# Sheet2_Power_Supply.net
KiCad netlist of a schematic drawn in Altium Designer
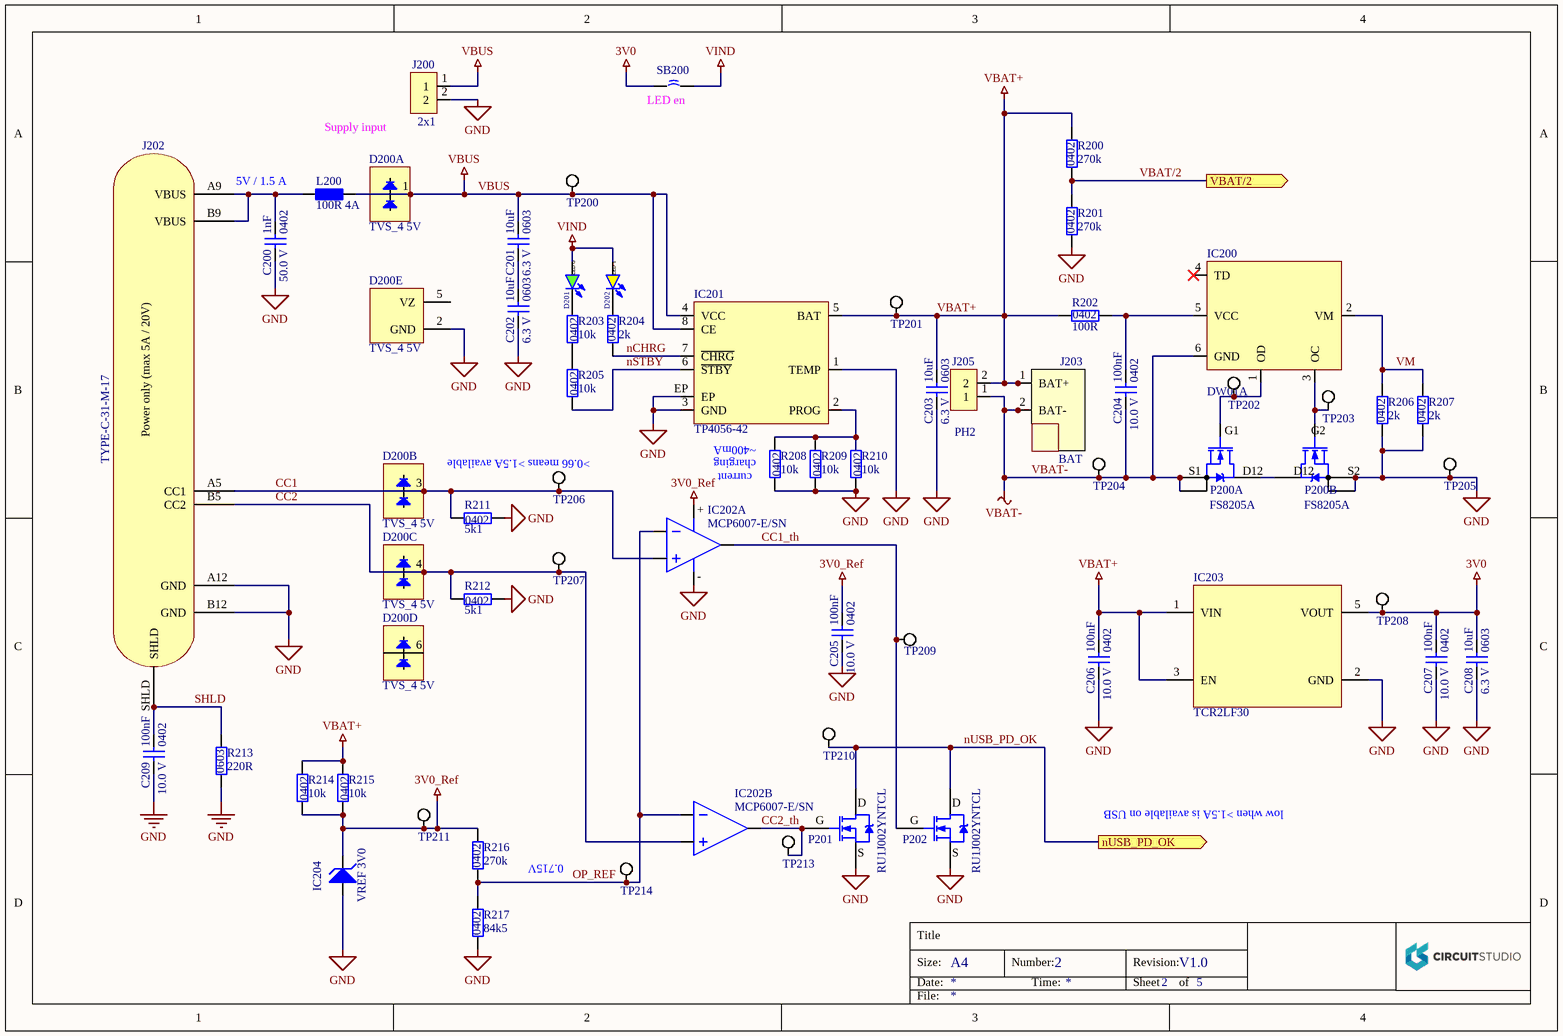
[diagram p0: Sheet2_Power_Supply.SchDoc]

(export (version "E")
  (design (tool "Eeschema 10.0.6"))
  (components
    (comp (ref "C200")
      (value "C 1nF 0402 50V")
      (footprint "0402")
      (description "CAP CER 1000PF 50V C0G/NP0 0402")
      (fields
        (field (name "MANUFACTURER") "Murata Electronics")
        (field (name "MANUFACTURER PART NUMBER") "GRM1555C1H102JA01J")
        (field (name "CAPACITANCE") "1nF")
        (field (name "VOLTAGE") "50.0 V")
      )
      (libsource (lib "CS_Part_Library") (part "CAP_1nF_50V_0402"))
    )
    (comp (ref "C201")
      (value "C 10uF 0603 6.3V")
      (footprint "0603")
      (description "CAP CER 10UF 6.3V X5R 0603")
      (fields
        (field (name "MANUFACTURER") "Taiyo Yuden")
        (field (name "MANUFACTURER PART NUMBER") "JMK107ABJ106MA-T")
        (field (name "CAPACITANCE") "10uF")
        (field (name "VOLTAGE") "6.3 V")
      )
      (libsource (lib "CS_Part_Library") (part "CAP_10uF_6V3_0603"))
    )
    (comp (ref "C202")
      (value "C 10uF 0603 6.3V")
      (footprint "0603")
      (description "CAP CER 10UF 6.3V X5R 0603")
      (fields
        (field (name "MANUFACTURER") "Taiyo Yuden")
        (field (name "MANUFACTURER PART NUMBER") "JMK107ABJ106MA-T")
        (field (name "CAPACITANCE") "10uF")
        (field (name "VOLTAGE") "6.3 V")
      )
      (libsource (lib "CS_Part_Library") (part "CAP_10uF_6V3_0603"))
    )
    (comp (ref "C203")
      (value "C 10uF 0603 6.3V")
      (footprint "0603")
      (description "CAP CER 10UF 6.3V X5R 0603")
      (fields
        (field (name "MANUFACTURER") "Taiyo Yuden")
        (field (name "MANUFACTURER PART NUMBER") "JMK107ABJ106MA-T")
        (field (name "CAPACITANCE") "10uF")
        (field (name "VOLTAGE") "6.3 V")
      )
      (libsource (lib "CS_Part_Library") (part "CAP_10uF_6V3_0603"))
    )
    (comp (ref "C204")
      (value "C 100nF 0402 10V")
      (footprint "0402")
      (description "CAP CER 0.1UF 10V X5R 0402")
      (fields
        (field (name "MANUFACTURER") "Samsung Electro-Mechanics")
        (field (name "MANUFACTURER PART NUMBER") "CL05A104MP5NNNC")
        (field (name "CAPACITANCE") "100nF")
        (field (name "VOLTAGE") "10.0 V")
      )
      (libsource (lib "CS_Part_Library") (part "CAP_100nF_10V_0402"))
    )
    (comp (ref "C205")
      (value "C 100nF 0402 10V")
      (footprint "0402")
      (description "CAP CER 0.1UF 10V X5R 0402")
      (fields
        (field (name "MANUFACTURER") "Samsung Electro-Mechanics")
        (field (name "MANUFACTURER PART NUMBER") "CL05A104MP5NNNC")
        (field (name "CAPACITANCE") "100nF")
        (field (name "VOLTAGE") "10.0 V")
      )
      (libsource (lib "CS_Part_Library") (part "CAP_100nF_10V_0402"))
    )
    (comp (ref "C206")
      (value "C 100nF 0402 10V")
      (footprint "0402")
      (description "CAP CER 0.1UF 10V X5R 0402")
      (fields
        (field (name "MANUFACTURER") "Samsung Electro-Mechanics")
        (field (name "MANUFACTURER PART NUMBER") "CL05A104MP5NNNC")
        (field (name "CAPACITANCE") "100nF")
        (field (name "VOLTAGE") "10.0 V")
      )
      (libsource (lib "CS_Part_Library") (part "CAP_100nF_10V_0402"))
    )
    (comp (ref "C207")
      (value "C 100nF 0402 10V")
      (footprint "0402")
      (description "CAP CER 0.1UF 10V X5R 0402")
      (fields
        (field (name "MANUFACTURER") "Samsung Electro-Mechanics")
        (field (name "MANUFACTURER PART NUMBER") "CL05A104MP5NNNC")
        (field (name "CAPACITANCE") "100nF")
        (field (name "VOLTAGE") "10.0 V")
      )
      (libsource (lib "CS_Part_Library") (part "CAP_100nF_10V_0402"))
    )
    (comp (ref "C208")
      (value "C 10uF 0603 6.3V")
      (footprint "0603")
      (description "CAP CER 10UF 6.3V X5R 0603")
      (fields
        (field (name "MANUFACTURER") "Taiyo Yuden")
        (field (name "MANUFACTURER PART NUMBER") "JMK107ABJ106MA-T")
        (field (name "CAPACITANCE") "10uF")
        (field (name "VOLTAGE") "6.3 V")
      )
      (libsource (lib "CS_Part_Library") (part "CAP_10uF_6V3_0603"))
    )
    (comp (ref "C209")
      (value "C 100nF 0402 10V")
      (footprint "0402")
      (description "CAP CER 0.1UF 10V X5R 0402")
      (fields
        (field (name "MANUFACTURER") "Samsung Electro-Mechanics")
        (field (name "MANUFACTURER PART NUMBER") "CL05A104MP5NNNC")
        (field (name "CAPACITANCE") "100nF")
        (field (name "VOLTAGE") "10.0 V")
      )
      (libsource (lib "CS_Part_Library") (part "CAP_100nF_10V_0402"))
    )
    (comp (ref "D200")
      (value "TVS_4 5V")
      (footprint "SOT-23-6")
      (description "TVS DIODE 5VWM 12.5VC SOT23-6")
      (fields
        (field (name "MANUFACTURER") "Comchip Technology")
        (field (name "MANUFACTURER PART NUMBER") "CPDT6-5V0UPC-HF")
      )
      (libsource (lib "CS_Part_Library") (part "D_TVS_U4_12V5"))
    )
    (comp (ref "D201")
      (value "LED G")
      (footprint "LED_0603")
      (description "LED GREEN DIFFUSED 0603 SMD")
      (fields
        (field (name "MANUFACTURER") "OSRAM Opto Semiconductors Inc.")
        (field (name "MANUFACTURER PART NUMBER") "LT Q39G-Q1OO-25-1")
      )
      (libsource (lib "CS_Part_Library") (part "D_LED_Green_0603"))
    )
    (comp (ref "D202")
      (value "LED Y")
      (footprint "LED_0603")
      (description "LED YELLOW DIFFUSED")
      (fields
        (field (name "MANUFACTURER") "Stanley Electric Co")
        (field (name "MANUFACTURER PART NUMBER") "FKY1111C-TR")
      )
      (libsource (lib "CS_Part_Library") (part "D_LED_Yellow_0603"))
    )
    (comp (ref "IC200")
      (value "DW01A")
      (footprint "SOT-23-6")
      (description "IC BATT MANAGEMENT SOT-23-6")
      (fields (field (name "MANUFACTURER") "PUOLOP"))
      (libsource (lib "Symbols") (part "IC_BAT_PROT_DW01A"))
    )
    (comp (ref "IC201")
      (value "TP4056-42")
      (footprint "SOIC-8-EP")
      (description "IC BATT CHG LI-ION 1CELL ESOP-8-EP")
      (fields
        (field (name "MANUFACTURER") "TOPPOWER(Nanjing Extension Microelectronics)")
        (field (name "MANUFACTURER PART NUMBER") "TP4056-42-ESOP8")
      )
      (libsource (lib "Symbols") (part "IC_BAT_CHGR_TP4056"))
    )
    (comp (ref "IC202")
      (value "MCP6007-E/SN")
      (footprint "SOIC-8")
      (description "DUAL, 1MHZ OP AMP, E TEMP")
      (fields (field (name "MANUFACTURER") "Microchip Technology"))
      (libsource (lib "CS_Part_Library") (part "IC_OpAmp_MCP6007-E/SN"))
    )
    (comp (ref "IC203")
      (value "TCR2LF30")
      (footprint "SOT-23-5")
      (description "IC REG LINEAR 3V 200MA SMV")
      (fields
        (field (name "MANUFACTURER") "Toshiba Semiconductor and Storage")
        (field (name "MANUFACTURER PART NUMBER") "TCR2LF30,LM(CT")
      )
      (libsource (lib "CS_Part_Library") (part "IC_Reg_TCR2LF30"))
    )
    (comp (ref "IC204")
      (value "VREF 3V0")
      (footprint "SOT-23-3")
      (description "IC VREF SHUNT 1% SOT23-3")
      (fields
        (field (name "MANUFACTURER") "Texas Instruments")
        (field (name "MANUFACTURER PART NUMBER") "LM4040DIM3X-3.0/NOPB")
      )
      (libsource (lib "Symbols") (part "IC_Ref_LM4040DIM3X-3.0"))
    )
    (comp (ref "J200")
      (value "2x1")
      (footprint "PH_1x2")
      (description "CONN HEADER VERT 2POS 2.54MM")
      (fields
        (field (name "MANUFACTURER") "Sullins Connector Solutions")
        (field (name "MANUFACTURER PART NUMBER") "PRPC002SAAN-RC")
      )
      (libsource (lib "CS_Part_Library") (part "J_MH2x1_2.54"))
    )
    (comp (ref "J202")
      (value "TYPE-C-31-M-17")
      (footprint "Con_TYPE-C-31-M-17")
      (description "USB4 GEN3, TYPE C, TOP MOUNT")
      (fields (field (name "MANUFACTURER") "Korean Hroparts Elec"))
      (libsource (lib "Symbols") (part "J_USB-C_2"))
    )
    (comp (ref "J203")
      (value "BAT")
      (footprint "J_BAT_CLIP_18650")
      (description "SMT Battery Connectors 18650")
      (fields (field (name "MANUFACTURER") "MYOUNG") (field (name "MANUFACTURER PART NUMBER") "MY-18650-02"))
      (libsource (lib "CS_Part_Library") (part "J_BAT_CLIP_18650_A"))
    )
    (comp (ref "J204")
      (value "BAT")
      (description "SMT Battery Connectors 18650")
      (fields (field (name "MANUFACTURER") "MYOUNG") (field (name "MANUFACTURER PART NUMBER") "MY-18650-02"))
      (libsource (lib "CS_Part_Library") (part "J_BAT_CLIP_18650_B"))
    )
    (comp (ref "J205")
      (value "PH2")
      (footprint "J_S2B-PH-K-S")
      (description "CONN HEADER R/A 2POS 2MM")
      (fields
        (field (name "MANUFACTURER") "JST Sales America Inc.")
        (field (name "MANUFACTURER PART NUMBER") "S2B-PH-KL(LF)(SN)")
      )
      (libsource (lib "Symbols") (part "J_S2B-PH-KL"))
    )
    (comp (ref "L200")
      (value "L Ferrite 100R 4A")
      (footprint "L_1206")
      (description "FIXED IND 100 4000MA 1206")
      (fields
        (field (name "MANUFACTURER") "Eaton - Electronics Division")
        (field (name "MANUFACTURER PART NUMBER") "MFBM1V3216-101-R")
        (field (name "INDUCTANCE") "100R 4A")
      )
      (libsource (lib "CS_Part_Library") (part "L_100R_4A"))
    )
    (comp (ref "P200")
      (value "P2 NMOS 20V 6A")
      (footprint "TSSOP-8_4.4mm")
      (description "MOSFET 2N_CH 20V 6A TSSOP-8")
      (fields
        (field (name "MANUFACTURER") "Fortune Semicon")
        (field (name "MANUFACTURER PART NUMBER") "FS8205A")
      )
      (libsource (lib "Symbols") (part "P_2NCH_20V_1W"))
    )
    (comp (ref "P201")
      (value "P_NCH_50V_150mW")
      (footprint "UMT3F")
      (description "MOSFET N-CH 50V 200MA UMT3F")
      (fields
        (field (name "MANUFACTURER") "Rohm Semiconductor")
        (field (name "MANUFACTURER PART NUMBER") "RU1J002YNTCL")
      )
      (libsource (lib "CS_Part_Library") (part "P_NCH_50V_150mW"))
    )
    (comp (ref "P202")
      (value "P_NCH_50V_150mW")
      (footprint "UMT3F")
      (description "MOSFET N-CH 50V 200MA UMT3F")
      (fields
        (field (name "MANUFACTURER") "Rohm Semiconductor")
        (field (name "MANUFACTURER PART NUMBER") "RU1J002YNTCL")
      )
      (libsource (lib "CS_Part_Library") (part "P_NCH_50V_150mW"))
    )
    (comp (ref "R200")
      (value "R 270k 0402")
      (footprint "0402")
      (description "RES 270K OHM 1% 1/16W 0402")
      (fields
        (field (name "MANUFACTURER") "YAGEO")
        (field (name "MANUFACTURER PART NUMBER") "RC0402FR-07270KL")
        (field (name "RESISTANCE") "270k")
      )
      (libsource (lib "CS_Part_Library") (part "R_270k_0402"))
    )
    (comp (ref "R201")
      (value "R 270k 0402")
      (footprint "0402")
      (description "RES 270K OHM 1% 1/16W 0402")
      (fields
        (field (name "MANUFACTURER") "YAGEO")
        (field (name "MANUFACTURER PART NUMBER") "RC0402FR-07270KL")
        (field (name "RESISTANCE") "270k")
      )
      (libsource (lib "CS_Part_Library") (part "R_270k_0402"))
    )
    (comp (ref "R202")
      (value "R 100R 0402")
      (footprint "0402")
      (description "RES 100 OHM 1% 1/16W 0402")
      (fields
        (field (name "MANUFACTURER") "Stackpole Electronics Inc")
        (field (name "MANUFACTURER PART NUMBER") "RMCF0402FT100R")
        (field (name "RESISTANCE") "100R")
      )
      (libsource (lib "CS_Part_Library") (part "R_100R_0402"))
    )
    (comp (ref "R203")
      (value "R 10k 0402")
      (footprint "0402")
      (description "RES 10K OHM 1% 1/16W 0402")
      (fields
        (field (name "MANUFACTURER") "YAGEO")
        (field (name "MANUFACTURER PART NUMBER") "RC0402FR-0710KL")
        (field (name "RESISTANCE") "10k")
      )
      (libsource (lib "CS_Part_Library") (part "R_10k_0402"))
    )
    (comp (ref "R204")
      (value "R 2k 0402")
      (footprint "0402")
      (description "RES 2K OHM 1% 1/16W 0402")
      (fields
        (field (name "MANUFACTURER") "Stackpole Electronics Inc")
        (field (name "MANUFACTURER PART NUMBER") "RMCF0402FT2K00")
        (field (name "RESISTANCE") "2k")
      )
      (libsource (lib "CS_Part_Library") (part "R_2k_0402"))
    )
    (comp (ref "R205")
      (value "R 10k 0402")
      (footprint "0402")
      (description "RES 10K OHM 1% 1/16W 0402")
      (fields
        (field (name "MANUFACTURER") "YAGEO")
        (field (name "MANUFACTURER PART NUMBER") "RC0402FR-0710KL")
        (field (name "RESISTANCE") "10k")
      )
      (libsource (lib "CS_Part_Library") (part "R_10k_0402"))
    )
    (comp (ref "R206")
      (value "R 2k 0402")
      (footprint "0402")
      (description "RES 2K OHM 1% 1/16W 0402")
      (fields
        (field (name "MANUFACTURER") "Stackpole Electronics Inc")
        (field (name "MANUFACTURER PART NUMBER") "RMCF0402FT2K00")
        (field (name "RESISTANCE") "2k")
      )
      (libsource (lib "CS_Part_Library") (part "R_2k_0402"))
    )
    (comp (ref "R207")
      (value "R 2k 0402")
      (footprint "0402")
      (description "RES 2K OHM 1% 1/16W 0402")
      (fields
        (field (name "MANUFACTURER") "Stackpole Electronics Inc")
        (field (name "MANUFACTURER PART NUMBER") "RMCF0402FT2K00")
        (field (name "RESISTANCE") "2k")
      )
      (libsource (lib "CS_Part_Library") (part "R_2k_0402"))
    )
    (comp (ref "R208")
      (value "R 10k 0402")
      (footprint "0402")
      (description "RES 10K OHM 1% 1/16W 0402")
      (fields
        (field (name "MANUFACTURER") "YAGEO")
        (field (name "MANUFACTURER PART NUMBER") "RC0402FR-0710KL")
        (field (name "RESISTANCE") "10k")
      )
      (libsource (lib "CS_Part_Library") (part "R_10k_0402"))
    )
    (comp (ref "R209")
      (value "R 10k 0402")
      (footprint "0402")
      (description "RES 10K OHM 1% 1/16W 0402")
      (fields
        (field (name "MANUFACTURER") "YAGEO")
        (field (name "MANUFACTURER PART NUMBER") "RC0402FR-0710KL")
        (field (name "RESISTANCE") "10k")
      )
      (libsource (lib "CS_Part_Library") (part "R_10k_0402"))
    )
    (comp (ref "R210")
      (value "R 10k 0402")
      (footprint "0402")
      (description "RES 10K OHM 1% 1/16W 0402")
      (fields
        (field (name "MANUFACTURER") "YAGEO")
        (field (name "MANUFACTURER PART NUMBER") "RC0402FR-0710KL")
        (field (name "RESISTANCE") "10k")
      )
      (libsource (lib "CS_Part_Library") (part "R_10k_0402"))
    )
    (comp (ref "R211")
      (value "R 5k1 0402")
      (footprint "0402")
      (description "RES 5.1K OHM 1% 1/16W 0402")
      (fields
        (field (name "MANUFACTURER") "Stackpole Electronics Inc")
        (field (name "MANUFACTURER PART NUMBER") "RMCF0402FT5K10")
        (field (name "RESISTANCE") "5k1")
      )
      (libsource (lib "CS_Part_Library") (part "R_5k1_0420"))
    )
    (comp (ref "R212")
      (value "R 5k1 0402")
      (footprint "0402")
      (description "RES 5.1K OHM 1% 1/16W 0402")
      (fields
        (field (name "MANUFACTURER") "Stackpole Electronics Inc")
        (field (name "MANUFACTURER PART NUMBER") "RMCF0402FT5K10")
        (field (name "RESISTANCE") "5k1")
      )
      (libsource (lib "CS_Part_Library") (part "R_5k1_0420"))
    )
    (comp (ref "R213")
      (value "R 220R 0603")
      (footprint "0603")
      (description "RES 220 OHM 1% 1/10W 0603")
      (fields
        (field (name "MANUFACTURER") "Stackpole Electronics Inc")
        (field (name "MANUFACTURER PART NUMBER") "RMCF0603FT220R")
        (field (name "RESISTANCE") "220R")
      )
      (libsource (lib "CS_Part_Library") (part "R_220R_0603"))
    )
    (comp (ref "R214")
      (value "R 10k 0402")
      (footprint "0402")
      (description "RES 10K OHM 1% 1/16W 0402")
      (fields
        (field (name "MANUFACTURER") "YAGEO")
        (field (name "MANUFACTURER PART NUMBER") "RC0402FR-0710KL")
        (field (name "RESISTANCE") "10k")
      )
      (libsource (lib "CS_Part_Library") (part "R_10k_0402"))
    )
    (comp (ref "R215")
      (value "R 10k 0402")
      (footprint "0402")
      (description "RES 10K OHM 1% 1/16W 0402")
      (fields
        (field (name "MANUFACTURER") "YAGEO")
        (field (name "MANUFACTURER PART NUMBER") "RC0402FR-0710KL")
        (field (name "RESISTANCE") "10k")
      )
      (libsource (lib "CS_Part_Library") (part "R_10k_0402"))
    )
    (comp (ref "R216")
      (value "R 270k 0402")
      (footprint "0402")
      (description "RES 270K OHM 1% 1/16W 0402")
      (fields
        (field (name "MANUFACTURER") "YAGEO")
        (field (name "MANUFACTURER PART NUMBER") "RC0402FR-07270KL")
        (field (name "RESISTANCE") "270k")
      )
      (libsource (lib "CS_Part_Library") (part "R_270k_0402"))
    )
    (comp (ref "R217")
      (value "R 84k5 0402")
      (footprint "0402")
      (description "RES SMD 84.5K OHM 1% 1/16W 0402")
      (fields
        (field (name "MANUFACTURER") "Vishay Dale")
        (field (name "MANUFACTURER PART NUMBER") "CRCW040284K5FKED")
        (field (name "RESISTANCE") "84k5")
      )
      (libsource (lib "CS_Part_Library") (part "R_84k5_0402"))
    )
    (comp (ref "SB200")
      (value "SB")
      (footprint "SB_2_1mm_nc")
      (description "Solder Bridge sel2, normally closed")
      (libsource (lib "CS_Part_Library") (part "SB_sel2_1mm_nc"))
    )
    (comp (ref "TP200")
      (value "TP")
      (footprint "TP_1mm")
      (description "Test Point 1mm")
      (libsource (lib "CS_Part_Library") (part "TP_1mm"))
    )
    (comp (ref "TP201")
      (value "TP")
      (footprint "TP_1mm")
      (description "Test Point 1mm")
      (libsource (lib "CS_Part_Library") (part "TP_1mm"))
    )
    (comp (ref "TP202")
      (value "TP")
      (footprint "TP_1mm")
      (description "Test Point 1mm")
      (libsource (lib "CS_Part_Library") (part "TP_1mm"))
    )
    (comp (ref "TP203")
      (value "TP")
      (footprint "TP_1mm")
      (description "Test Point 1mm")
      (libsource (lib "CS_Part_Library") (part "TP_1mm"))
    )
    (comp (ref "TP204")
      (value "TP")
      (footprint "TP_1mm")
      (description "Test Point 1mm")
      (libsource (lib "CS_Part_Library") (part "TP_1mm"))
    )
    (comp (ref "TP205")
      (value "TP")
      (footprint "TP_1mm")
      (description "Test Point 1mm")
      (libsource (lib "CS_Part_Library") (part "TP_1mm"))
    )
    (comp (ref "TP206")
      (value "TP")
      (footprint "TP_1mm")
      (description "Test Point 1mm")
      (libsource (lib "CS_Part_Library") (part "TP_1mm"))
    )
    (comp (ref "TP207")
      (value "TP")
      (footprint "TP_1mm")
      (description "Test Point 1mm")
      (libsource (lib "CS_Part_Library") (part "TP_1mm"))
    )
    (comp (ref "TP208")
      (value "TP")
      (footprint "TP_1mm")
      (description "Test Point 1mm")
      (libsource (lib "CS_Part_Library") (part "TP_1mm"))
    )
    (comp (ref "TP209")
      (value "TP")
      (footprint "TP_1mm")
      (description "Test Point 1mm")
      (libsource (lib "CS_Part_Library") (part "TP_1mm"))
    )
    (comp (ref "TP210")
      (value "TP")
      (footprint "TP_1mm")
      (description "Test Point 1mm")
      (libsource (lib "CS_Part_Library") (part "TP_1mm"))
    )
    (comp (ref "TP211")
      (value "TP")
      (footprint "TP_1mm")
      (description "Test Point 1mm")
      (libsource (lib "CS_Part_Library") (part "TP_1mm"))
    )
    (comp (ref "TP213")
      (value "TP")
      (footprint "TP_1mm")
      (description "Test Point 1mm")
      (libsource (lib "CS_Part_Library") (part "TP_1mm"))
    )
    (comp (ref "TP214")
      (value "TP")
      (footprint "TP_1mm")
      (description "Test Point 1mm")
      (libsource (lib "CS_Part_Library") (part "TP_1mm"))
    )
  )
  (nets
    (net (code "1") (name "/CC1") (class "Default")
      (node (ref "D200") (pin "3") (pinfunction "3_3") (pintype "passive"))
      (node (ref "IC202") (pin "3") (pinfunction "INA+_3") (pintype "passive"))
      (node (ref "J202") (pin "A5") (pinfunction "CC1_A5") (pintype "passive"))
      (node (ref "R211") (pin "2") (pinfunction "2_2") (pintype "passive"))
      (node (ref "TP206") (pin "1") (pinfunction "TP_1") (pintype "passive"))
    )
    (net (code "2") (name "/CC1_th") (class "Default")
      (node (ref "IC202") (pin "1") (pinfunction "OUTA_1") (pintype "passive"))
      (node (ref "P202") (pin "1") (pinfunction "G_1") (pintype "passive"))
      (node (ref "TP209") (pin "1") (pinfunction "TP_1") (pintype "passive"))
    )
    (net (code "3") (name "/CC2") (class "Default")
      (node (ref "D200") (pin "4") (pinfunction "4_4") (pintype "passive"))
      (node (ref "IC202") (pin "5") (pinfunction "INB+_5") (pintype "passive"))
      (node (ref "J202") (pin "B5") (pinfunction "CC2_B5") (pintype "passive"))
      (node (ref "R212") (pin "2") (pinfunction "2_2") (pintype "passive"))
      (node (ref "TP207") (pin "1") (pinfunction "TP_1") (pintype "passive"))
    )
    (net (code "4") (name "/CC2_th") (class "Default")
      (node (ref "IC202") (pin "7") (pinfunction "OUTB_7") (pintype "passive"))
      (node (ref "P201") (pin "1") (pinfunction "G_1") (pintype "passive"))
      (node (ref "TP213") (pin "1") (pinfunction "TP_1") (pintype "passive"))
    )
    (net (code "5") (name "/OP_REF") (class "Default")
      (node (ref "IC202") (pin "2") (pinfunction "INA-_2") (pintype "passive"))
      (node (ref "IC202") (pin "6") (pinfunction "INB-_6") (pintype "passive"))
      (node (ref "R216") (pin "1") (pinfunction "1_1") (pintype "passive"))
      (node (ref "R217") (pin "2") (pinfunction "2_2") (pintype "passive"))
      (node (ref "TP214") (pin "1") (pinfunction "TP_1") (pintype "passive"))
    )
    (net (code "6") (name "/SHLD") (class "Default")
      (node (ref "C209") (pin "2") (pinfunction "2_2") (pintype "passive"))
      (node (ref "J202") (pin "SHLD") (pinfunction "SHLD_SHLD") (pintype "passive"))
      (node (ref "R213") (pin "2") (pinfunction "2_2") (pintype "passive"))
    )
    (net (code "7") (name "/VBAT{slash}2") (class "Default")
      (node (ref "R200") (pin "1") (pinfunction "1_1") (pintype "passive"))
      (node (ref "R201") (pin "2") (pinfunction "2_2") (pintype "passive"))
    )
    (net (code "8") (name "/VM") (class "Default")
      (node (ref "IC200") (pin "2") (pinfunction "VM_2") (pintype "passive"))
      (node (ref "R206") (pin "2") (pinfunction "2_2") (pintype "passive"))
      (node (ref "R207") (pin "2") (pinfunction "2_2") (pintype "passive"))
    )
    (net (code "9") (name "/nCHRG") (class "Default")
      (node (ref "IC201") (pin "7") (pinfunction "~{CHRG}_7") (pintype "passive"))
      (node (ref "R204") (pin "1") (pinfunction "1_1") (pintype "passive"))
    )
    (net (code "10") (name "/nSTBY") (class "Default")
      (node (ref "IC201") (pin "6") (pinfunction "~{STBY}_6") (pintype "passive"))
      (node (ref "R205") (pin "1") (pinfunction "1_1") (pintype "passive"))
    )
    (net (code "11") (name "/nUSB_PD_OK") (class "Default")
      (node (ref "P201") (pin "3") (pinfunction "D_3") (pintype "passive"))
      (node (ref "P202") (pin "3") (pinfunction "D_3") (pintype "passive"))
      (node (ref "TP210") (pin "1") (pinfunction "TP_1") (pintype "passive"))
    )
    (net (code "12") (name "3V0") (class "Default")
      (node (ref "C207") (pin "2") (pinfunction "2_2") (pintype "passive"))
      (node (ref "C208") (pin "2") (pinfunction "2_2") (pintype "passive"))
      (node (ref "IC203") (pin "5") (pinfunction "VOUT_5") (pintype "passive"))
      (node (ref "SB200") (pin "1") (pinfunction "1_1") (pintype "passive"))
      (node (ref "TP208") (pin "1") (pinfunction "TP_1") (pintype "passive"))
    )
    (net (code "13") (name "3V0_Ref") (class "Default")
      (node (ref "C205") (pin "2") (pinfunction "2_2") (pintype "passive"))
      (node (ref "IC202") (pin "8") (pinfunction "VDD_8") (pintype "passive"))
      (node (ref "IC204") (pin "1") (pinfunction "K_1") (pintype "passive"))
      (node (ref "R214") (pin "1") (pinfunction "1_1") (pintype "passive"))
      (node (ref "R215") (pin "1") (pinfunction "1_1") (pintype "passive"))
      (node (ref "R216") (pin "2") (pinfunction "2_2") (pintype "passive"))
      (node (ref "TP211") (pin "1") (pinfunction "TP_1") (pintype "passive"))
    )
    (net (code "14") (name "GND") (class "Default")
      (node (ref "C200") (pin "1") (pinfunction "1_1") (pintype "passive"))
      (node (ref "C202") (pin "1") (pinfunction "1_1") (pintype "passive"))
      (node (ref "C203") (pin "1") (pinfunction "1_1") (pintype "passive"))
      (node (ref "C205") (pin "1") (pinfunction "1_1") (pintype "passive"))
      (node (ref "C206") (pin "1") (pinfunction "1_1") (pintype "passive"))
      (node (ref "C207") (pin "1") (pinfunction "1_1") (pintype "passive"))
      (node (ref "C208") (pin "1") (pinfunction "1_1") (pintype "passive"))
      (node (ref "C209") (pin "1") (pinfunction "1_1") (pintype "passive"))
      (node (ref "D200") (pin "2") (pinfunction "GND_2") (pintype "passive"))
      (node (ref "IC201") (pin "1") (pinfunction "TEMP_1") (pintype "passive"))
      (node (ref "IC201") (pin "3") (pinfunction "GND_3") (pintype "passive"))
      (node (ref "IC201") (pin "EP") (pinfunction "EP_EP") (pintype "passive"))
      (node (ref "IC202") (pin "4") (pinfunction "VSS_4") (pintype "passive"))
      (node (ref "IC203") (pin "2") (pinfunction "GND_2") (pintype "passive"))
      (node (ref "IC204") (pin "2") (pinfunction "A_2") (pintype "passive"))
      (node (ref "J200") (pin "2") (pinfunction "2_2") (pintype "passive"))
      (node (ref "J202") (pin "A12") (pinfunction "GND_A12") (pintype "passive"))
      (node (ref "J202") (pin "B12") (pinfunction "GND_B12") (pintype "passive"))
      (node (ref "P200") (pin "6") (pinfunction "S2_6") (pintype "passive"))
      (node (ref "P200") (pin "7") (pinfunction "S2_7") (pintype "passive"))
      (node (ref "P201") (pin "2") (pinfunction "S_2") (pintype "passive"))
      (node (ref "P202") (pin "2") (pinfunction "S_2") (pintype "passive"))
      (node (ref "R201") (pin "1") (pinfunction "1_1") (pintype "passive"))
      (node (ref "R206") (pin "1") (pinfunction "1_1") (pintype "passive"))
      (node (ref "R207") (pin "1") (pinfunction "1_1") (pintype "passive"))
      (node (ref "R208") (pin "1") (pinfunction "1_1") (pintype "passive"))
      (node (ref "R209") (pin "1") (pinfunction "1_1") (pintype "passive"))
      (node (ref "R210") (pin "1") (pinfunction "1_1") (pintype "passive"))
      (node (ref "R211") (pin "1") (pinfunction "1_1") (pintype "passive"))
      (node (ref "R212") (pin "1") (pinfunction "1_1") (pintype "passive"))
      (node (ref "R213") (pin "1") (pinfunction "1_1") (pintype "passive"))
      (node (ref "R217") (pin "1") (pinfunction "1_1") (pintype "passive"))
      (node (ref "TP205") (pin "1") (pinfunction "TP_1") (pintype "passive"))
    )
    (net (code "15") (name "Net-(C200-Pad2)") (class "Default")
      (node (ref "C200") (pin "2") (pinfunction "2_2") (pintype "passive"))
      (node (ref "J202") (pin "A9") (pinfunction "VBUS_A9") (pintype "passive"))
      (node (ref "J202") (pin "B9") (pinfunction "VBUS_B9") (pintype "passive"))
      (node (ref "L200") (pin "1") (pinfunction "1_1") (pintype "passive"))
    )
    (net (code "16") (name "Net-(C201-Pad1)") (class "Default")
      (node (ref "C201") (pin "1") (pinfunction "1_1") (pintype "passive"))
      (node (ref "C202") (pin "2") (pinfunction "2_2") (pintype "passive"))
    )
    (net (code "17") (name "Net-(D201-PadK)") (class "Default")
      (node (ref "D201") (pin "K") (pinfunction "K_K") (pintype "passive"))
      (node (ref "R203") (pin "2") (pinfunction "2_2") (pintype "passive"))
    )
    (net (code "18") (name "Net-(D202-PadK)") (class "Default")
      (node (ref "D202") (pin "K") (pinfunction "K_K") (pintype "passive"))
      (node (ref "R204") (pin "2") (pinfunction "2_2") (pintype "passive"))
    )
    (net (code "19") (name "Net-(IC200-OC)") (class "Default")
      (node (ref "IC200") (pin "3") (pinfunction "OC_3") (pintype "passive"))
      (node (ref "P200") (pin "5") (pinfunction "G1_5") (pintype "passive"))
      (node (ref "TP203") (pin "1") (pinfunction "TP_1") (pintype "passive"))
    )
    (net (code "20") (name "Net-(IC200-OD)") (class "Default")
      (node (ref "IC200") (pin "1") (pinfunction "OD_1") (pintype "passive"))
      (node (ref "P200") (pin "4") (pinfunction "G1_4") (pintype "passive"))
      (node (ref "TP202") (pin "1") (pinfunction "TP_1") (pintype "passive"))
    )
    (net (code "21") (name "Net-(IC200-VCC)") (class "Default")
      (node (ref "C204") (pin "2") (pinfunction "2_2") (pintype "passive"))
      (node (ref "IC200") (pin "5") (pinfunction "VCC_5") (pintype "passive"))
      (node (ref "R202") (pin "2") (pinfunction "2_2") (pintype "passive"))
    )
    (net (code "22") (name "Net-(IC201-PROG)") (class "Default")
      (node (ref "IC201") (pin "2") (pinfunction "PROG_2") (pintype "passive"))
      (node (ref "R208") (pin "2") (pinfunction "2_2") (pintype "passive"))
      (node (ref "R209") (pin "2") (pinfunction "2_2") (pintype "passive"))
      (node (ref "R210") (pin "2") (pinfunction "2_2") (pintype "passive"))
    )
    (net (code "23") (name "Net-(P200A-D12)") (class "Default")
      (node (ref "P200") (pin "1") (pinfunction "D12_1") (pintype "passive"))
      (node (ref "P200") (pin "8") (pinfunction "D12_8") (pintype "passive"))
    )
    (net (code "24") (name "Net-(R203-Pad1)") (class "Default")
      (node (ref "R203") (pin "1") (pinfunction "1_1") (pintype "passive"))
      (node (ref "R205") (pin "2") (pinfunction "2_2") (pintype "passive"))
    )
    (net (code "25") (name "VBAT+") (class "Default")
      (node (ref "C203") (pin "2") (pinfunction "2_2") (pintype "passive"))
      (node (ref "C206") (pin "2") (pinfunction "2_2") (pintype "passive"))
      (node (ref "IC201") (pin "5") (pinfunction "BAT_5") (pintype "passive"))
      (node (ref "IC203") (pin "1") (pinfunction "VIN_1") (pintype "passive"))
      (node (ref "IC203") (pin "3") (pinfunction "EN_3") (pintype "passive"))
      (node (ref "J203") (pin "1") (pinfunction "BAT+_1") (pintype "passive"))
      (node (ref "J205") (pin "2") (pinfunction "2_2") (pintype "passive"))
      (node (ref "R200") (pin "2") (pinfunction "2_2") (pintype "passive"))
      (node (ref "R202") (pin "1") (pinfunction "1_1") (pintype "passive"))
      (node (ref "R214") (pin "2") (pinfunction "2_2") (pintype "passive"))
      (node (ref "R215") (pin "2") (pinfunction "2_2") (pintype "passive"))
      (node (ref "TP201") (pin "1") (pinfunction "TP_1") (pintype "passive"))
    )
    (net (code "26") (name "VBAT-") (class "Default")
      (node (ref "C204") (pin "1") (pinfunction "1_1") (pintype "passive"))
      (node (ref "IC200") (pin "6") (pinfunction "GND_6") (pintype "passive"))
      (node (ref "J203") (pin "2") (pinfunction "BAT-_2") (pintype "passive"))
      (node (ref "J205") (pin "1") (pinfunction "1_1") (pintype "passive"))
      (node (ref "P200") (pin "2") (pinfunction "S1_2") (pintype "passive"))
      (node (ref "P200") (pin "3") (pinfunction "S1_3") (pintype "passive"))
      (node (ref "TP204") (pin "1") (pinfunction "TP_1") (pintype "passive"))
    )
    (net (code "27") (name "VBUS") (class "Default")
      (node (ref "C201") (pin "2") (pinfunction "2_2") (pintype "passive"))
      (node (ref "D200") (pin "1") (pinfunction "1_1") (pintype "passive"))
      (node (ref "IC201") (pin "4") (pinfunction "VCC_4") (pintype "passive"))
      (node (ref "IC201") (pin "8") (pinfunction "CE_8") (pintype "passive"))
      (node (ref "J200") (pin "1") (pinfunction "1_1") (pintype "passive"))
      (node (ref "L200") (pin "2") (pinfunction "2_2") (pintype "passive"))
      (node (ref "TP200") (pin "1") (pinfunction "TP_1") (pintype "passive"))
    )
    (net (code "28") (name "VIND") (class "Default")
      (node (ref "D201") (pin "A") (pinfunction "A_A") (pintype "passive"))
      (node (ref "D202") (pin "A") (pinfunction "A_A") (pintype "passive"))
      (node (ref "SB200") (pin "2") (pinfunction "2_2") (pintype "passive"))
    )
    (net (code "29") (name "unconnected-(D200-Pad6)") (class "Default")
      (node (ref "D200") (pin "6") (pinfunction "6_6") (pintype "passive"))
    )
    (net (code "30") (name "unconnected-(D200E-VZ-Pad5)") (class "Default")
      (node (ref "D200") (pin "5") (pinfunction "VZ_5") (pintype "passive"))
    )
    (net (code "31") (name "unconnected-(IC200-TD-Pad4)") (class "Default")
      (node (ref "IC200") (pin "4") (pinfunction "TD_4") (pintype "passive+no_connect"))
    )
  )
)
